# LiPo_Lademodul.net
KiCad netlist of a schematic drawn in EAGLE
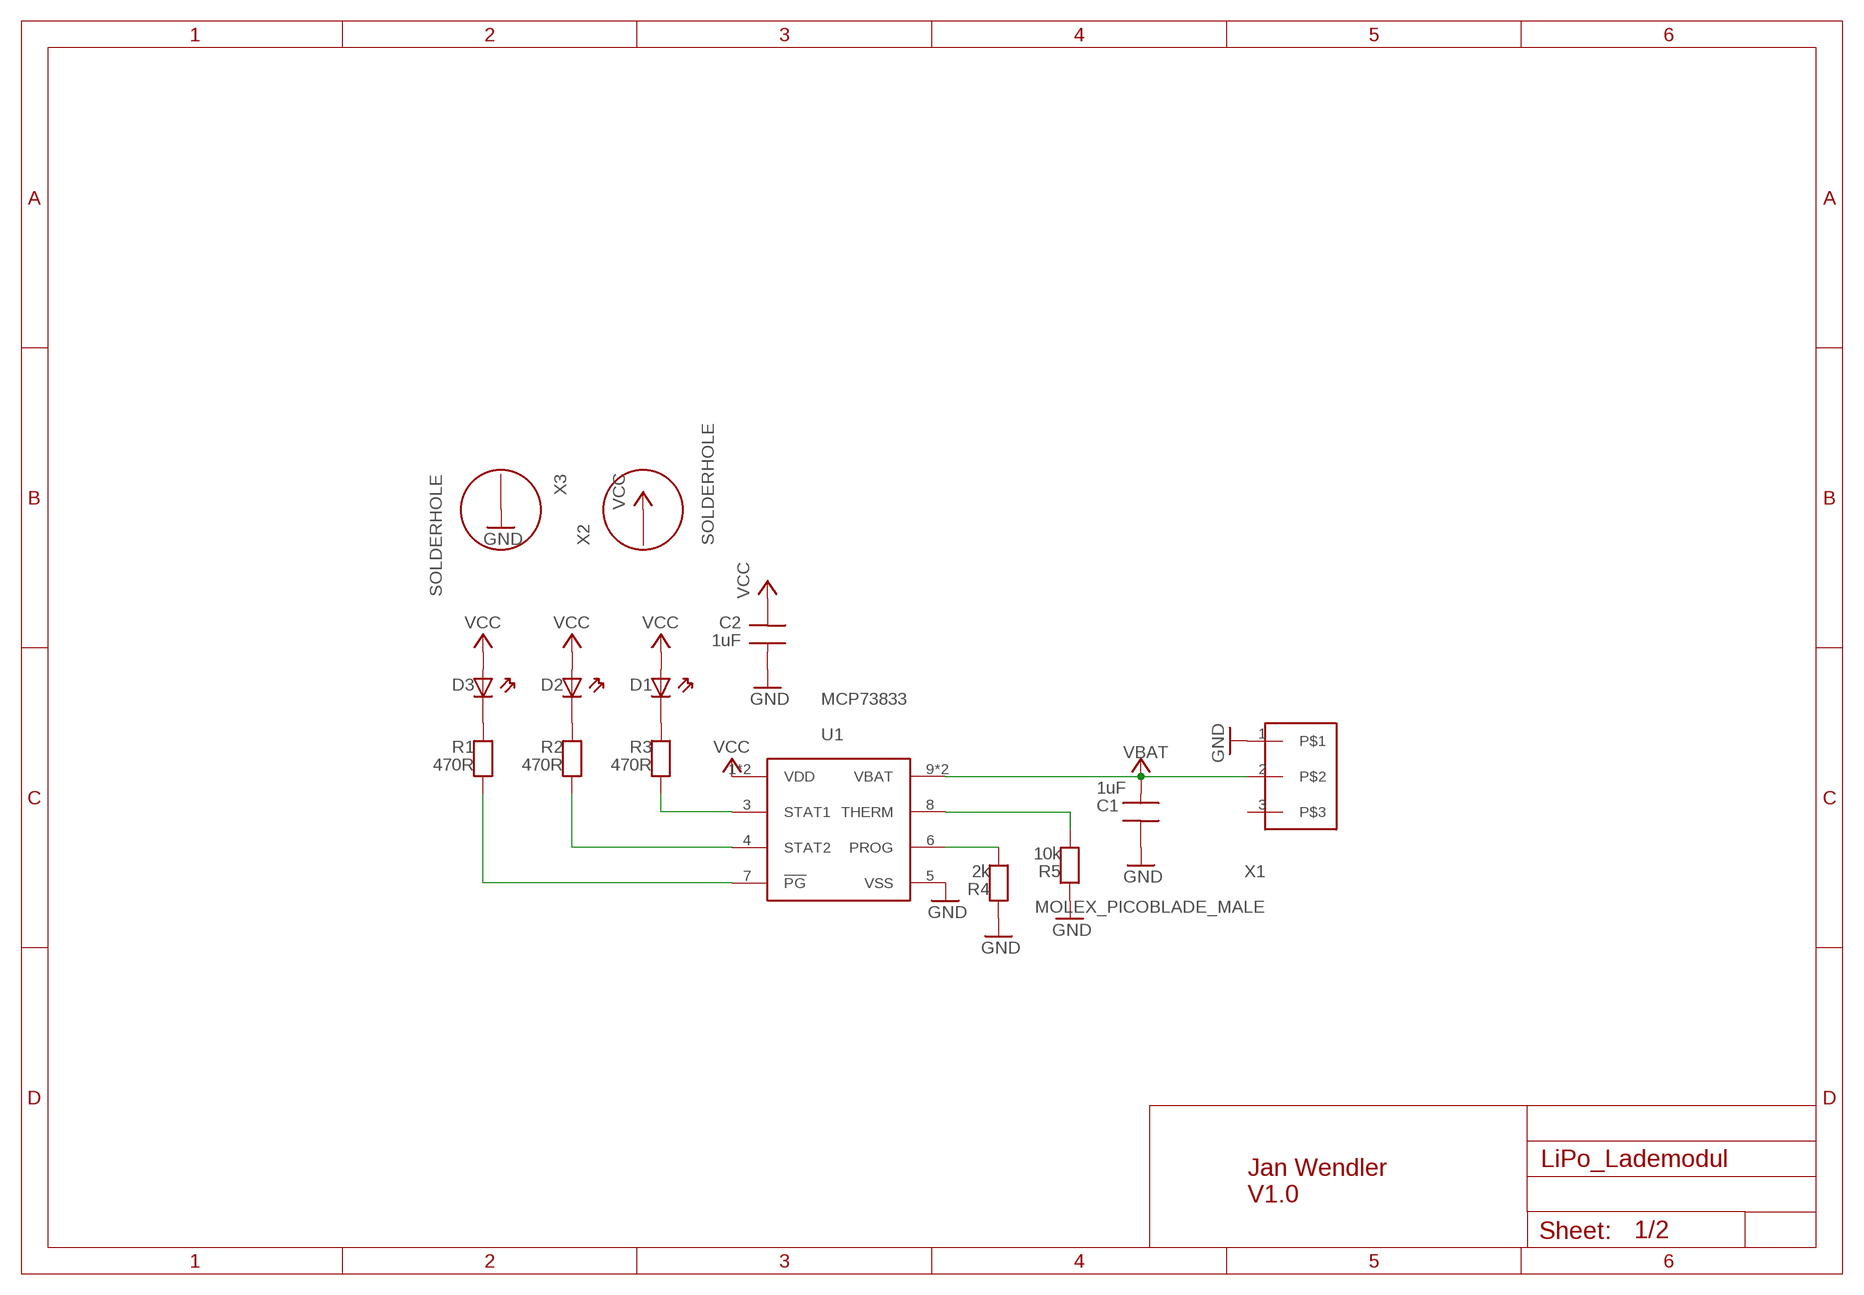
[diagram p0: schematic, sheet 1]

(export (version "E")
  (design (tool "Eeschema 10.0.6"))
  (components
    (comp (ref "C1")
      (value "1uF")
      (footprint "eagle-import:0603")
      (libsource (lib "eagle-import") (part "C0603"))
    )
    (comp (ref "C2")
      (value "1uF")
      (footprint "eagle-import:0603")
      (libsource (lib "eagle-import") (part "C0603"))
    )
    (comp (ref "D1")
      (value "D0603")
      (footprint "eagle-import:0603")
      (libsource (lib "eagle-import") (part "D0603"))
    )
    (comp (ref "D2")
      (value "D0603")
      (footprint "eagle-import:0603")
      (libsource (lib "eagle-import") (part "D0603"))
    )
    (comp (ref "D3")
      (value "D0603")
      (footprint "eagle-import:0603")
      (libsource (lib "eagle-import") (part "D0603"))
    )
    (comp (ref "R1")
      (value "470R")
      (footprint "eagle-import:0603")
      (libsource (lib "eagle-import") (part "R0603"))
    )
    (comp (ref "R2")
      (value "470R")
      (footprint "eagle-import:0603")
      (libsource (lib "eagle-import") (part "R0603"))
    )
    (comp (ref "R3")
      (value "470R")
      (footprint "eagle-import:0603")
      (libsource (lib "eagle-import") (part "R0603"))
    )
    (comp (ref "R4")
      (value "2k")
      (footprint "eagle-import:0603")
      (libsource (lib "eagle-import") (part "R0603"))
    )
    (comp (ref "R5")
      (value "10k")
      (footprint "eagle-import:0603")
      (libsource (lib "eagle-import") (part "R0603"))
    )
    (comp (ref "U1")
      (value "MCP73833")
      (footprint "eagle-import:MSOP10")
      (libsource (lib "eagle-import") (part "MCP73833"))
    )
    (comp (ref "X1")
      (value "MOLEX_PICOBLADE_MALE")
      (footprint "eagle-import:MOLEX_PICOBLADE_MALE")
      (libsource (lib "eagle-import") (part "MOLEX_PICOBLADE_MALE"))
    )
    (comp (ref "X2")
      (value "SOLDERHOLE")
      (footprint "eagle-import:HOLE_2MM")
      (libsource (lib "eagle-import") (part "SOLDERHOLE"))
    )
    (comp (ref "X3")
      (value "SOLDERHOLE")
      (footprint "eagle-import:HOLE_2MM")
      (libsource (lib "eagle-import") (part "SOLDERHOLE"))
    )
  )
  (nets
    (net (code "1") (name "GND") (class "Default")
      (node (ref "C1") (pin "2") (pinfunction "P$2_2") (pintype "bidirectional"))
      (node (ref "C2") (pin "1") (pinfunction "P$1_1") (pintype "bidirectional"))
      (node (ref "R4") (pin "1") (pinfunction "P$1_1") (pintype "bidirectional"))
      (node (ref "R5") (pin "1") (pinfunction "P$1_1") (pintype "bidirectional"))
      (node (ref "U1") (pin "5") (pinfunction "VSS_5") (pintype "bidirectional"))
      (node (ref "X1") (pin "1") (pinfunction "P$1_1") (pintype "bidirectional"))
      (node (ref "X3") (pin "P$1") (pinfunction "1_P$1") (pintype "bidirectional"))
    )
    (net (code "2") (name "Net-(D1-KATHODE)") (class "Default")
      (node (ref "D1") (pin "2") (pinfunction "KATHODE_2") (pintype "bidirectional"))
      (node (ref "R3") (pin "2") (pinfunction "P$2_2") (pintype "bidirectional"))
    )
    (net (code "3") (name "Net-(D2-KATHODE)") (class "Default")
      (node (ref "D2") (pin "2") (pinfunction "KATHODE_2") (pintype "bidirectional"))
      (node (ref "R2") (pin "2") (pinfunction "P$2_2") (pintype "bidirectional"))
    )
    (net (code "4") (name "Net-(D3-KATHODE)") (class "Default")
      (node (ref "D3") (pin "2") (pinfunction "KATHODE_2") (pintype "bidirectional"))
      (node (ref "R1") (pin "2") (pinfunction "P$2_2") (pintype "bidirectional"))
    )
    (net (code "5") (name "Net-(R1-P$1)") (class "Default")
      (node (ref "R1") (pin "1") (pinfunction "P$1_1") (pintype "bidirectional"))
      (node (ref "U1") (pin "7") (pinfunction "~{PG}_7") (pintype "bidirectional"))
    )
    (net (code "6") (name "Net-(R2-P$1)") (class "Default")
      (node (ref "R2") (pin "1") (pinfunction "P$1_1") (pintype "bidirectional"))
      (node (ref "U1") (pin "4") (pinfunction "STAT2_4") (pintype "bidirectional"))
    )
    (net (code "7") (name "Net-(R3-P$1)") (class "Default")
      (node (ref "R3") (pin "1") (pinfunction "P$1_1") (pintype "bidirectional"))
      (node (ref "U1") (pin "3") (pinfunction "STAT1_3") (pintype "bidirectional"))
    )
    (net (code "8") (name "Net-(R4-P$2)") (class "Default")
      (node (ref "R4") (pin "2") (pinfunction "P$2_2") (pintype "bidirectional"))
      (node (ref "U1") (pin "6") (pinfunction "PROG_6") (pintype "bidirectional"))
    )
    (net (code "9") (name "Net-(R5-P$2)") (class "Default")
      (node (ref "R5") (pin "2") (pinfunction "P$2_2") (pintype "bidirectional"))
      (node (ref "U1") (pin "8") (pinfunction "THERM_8") (pintype "bidirectional"))
    )
    (net (code "10") (name "VBAT") (class "Default")
      (node (ref "C1") (pin "1") (pinfunction "P$1_1") (pintype "bidirectional"))
      (node (ref "U1") (pin "10") (pinfunction "VBAT_10") (pintype "bidirectional"))
      (node (ref "U1") (pin "9") (pinfunction "VBAT_9") (pintype "bidirectional"))
      (node (ref "X1") (pin "2") (pinfunction "P$2_2") (pintype "bidirectional"))
    )
    (net (code "11") (name "VCC") (class "Default")
      (node (ref "C2") (pin "2") (pinfunction "P$2_2") (pintype "bidirectional"))
      (node (ref "D1") (pin "1") (pinfunction "ANODE_1") (pintype "bidirectional"))
      (node (ref "D2") (pin "1") (pinfunction "ANODE_1") (pintype "bidirectional"))
      (node (ref "D3") (pin "1") (pinfunction "ANODE_1") (pintype "bidirectional"))
      (node (ref "U1") (pin "1") (pinfunction "VDD_1") (pintype "bidirectional"))
      (node (ref "U1") (pin "2") (pinfunction "VDD_2") (pintype "bidirectional"))
      (node (ref "X2") (pin "P$1") (pinfunction "1_P$1") (pintype "bidirectional"))
    )
    (net (code "12") (name "unconnected-(X1-P$3-Pad3)") (class "Default")
      (node (ref "X1") (pin "3") (pinfunction "P$3_3") (pintype "bidirectional"))
    )
  )
)
